# DualDriverProp.net
KiCad netlist of a schematic drawn in Altium Designer
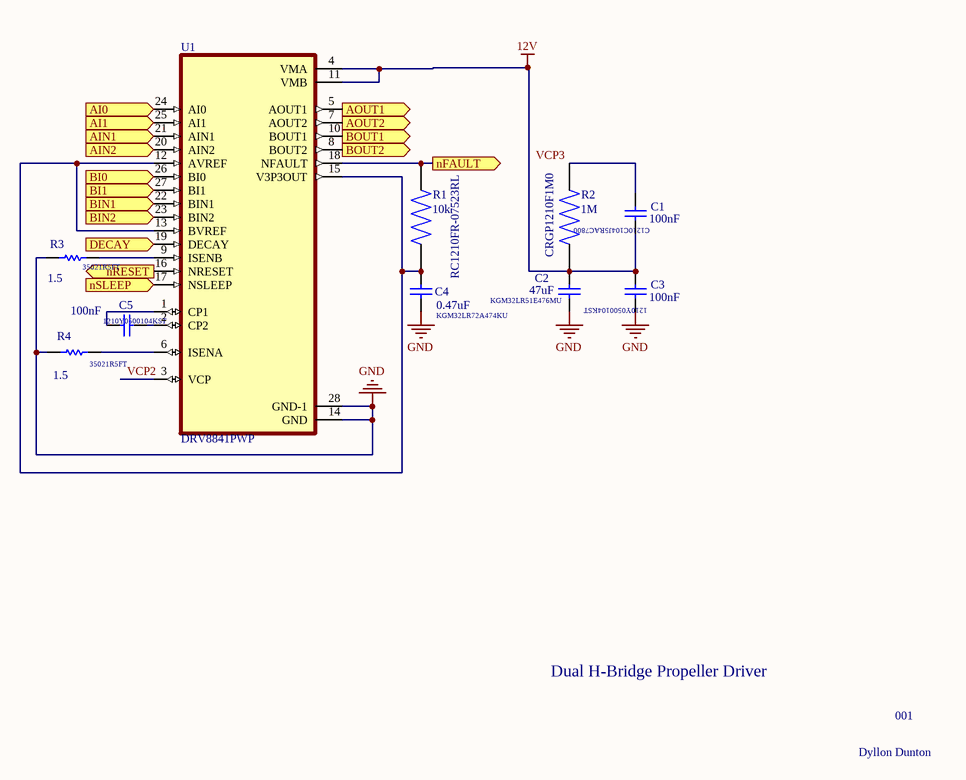
[diagram p0: DualDriverProp.SchDoc]

(export (version "E")
  (design (tool "Eeschema 10.0.6"))
  (components
    (comp (ref "C1")
      (value "100nF")
      (footprint "C1210")
      (description "Capacitor")
      (fields (field (name "Comment") "Cap") (field (name "PUBLISHER") "Altium Limited"))
      (libsource (lib "Miscellaneous Devices") (part "Cap"))
    )
    (comp (ref "C2")
      (value "47uF")
      (footprint "C1210")
      (description "Capacitor")
      (fields (field (name "Comment") "Cap") (field (name "PUBLISHER") "Altium Limited"))
      (libsource (lib "Miscellaneous Devices") (part "Cap"))
    )
    (comp (ref "C3")
      (value "100nF")
      (footprint "C1210")
      (description "Capacitor")
      (fields (field (name "Comment") "Cap") (field (name "PUBLISHER") "Altium Limited"))
      (libsource (lib "Miscellaneous Devices") (part "Cap"))
    )
    (comp (ref "C4")
      (value "0.47uF")
      (footprint "C1210")
      (description "Capacitor")
      (fields (field (name "Comment") "Cap") (field (name "PUBLISHER") "Altium Limited"))
      (libsource (lib "Miscellaneous Devices") (part "Cap"))
    )
    (comp (ref "C5")
      (value "100nF")
      (footprint "C1210")
      (description "Capacitor")
      (fields (field (name "Comment") "Cap") (field (name "PUBLISHER") "Altium Limited"))
      (libsource (lib "Miscellaneous Devices") (part "Cap"))
    )
    (comp (ref "R1")
      (value "RC1210FR-07523RL")
      (footprint "RESC3126X65N")
      (description "523 Ohms Â±1% 0.5W, 1/2W Chip Resistor 1210 _3225 Metric_ Moisture Resistant Thick Film")
      (fields (field (name "MF") "Yageo") (field (name "ALTIUM_VALUE") "10k"))
      (libsource (lib "RC1210FR-07523RL") (part "RC1210FR-07523RL"))
    )
    (comp (ref "R2")
      (value "CRGP1210F1M0")
      (footprint "RESC3126X65N")
      (description "523 Ohms Â±1% 0.5W, 1/2W Chip Resistor 1210 _3225 Metric_ Moisture Resistant Thick Film")
      (fields
        (field (name "MF") "Yageo")
        (field (name "ALTIUM_VALUE") "1M")
        (field (name "MP") "RC1210FR-07523RL")
      )
      (libsource (lib "RC1210FR-07523RL") (part "RC1210FR-07523RL"))
    )
    (comp (ref "R3")
      (value "1.5")
      (footprint "RESC5025X70N")
      (description "Resistor")
      (fields (field (name "Comment") "Res1") (field (name "PUBLISHER") "Altium Limited"))
      (libsource (lib "Miscellaneous Devices") (part "Res1"))
    )
    (comp (ref "R4")
      (value "1.5")
      (footprint "RESC5025X70N")
      (description "Resistor")
      (fields (field (name "Comment") "Res1") (field (name "PUBLISHER") "Altium Limited"))
      (libsource (lib "Miscellaneous Devices") (part "Res1"))
    )
    (comp (ref "U1")
      (value "DRV8841PWP")
      (footprint "IC_TPS61196PWPRQ1")
      (fields (field (name "MF") "Texas Instruments"))
      (libsource (lib "DRV8841PWP") (part "DRV8841PWP"))
    )
  )
  (nets
    (net (code "1") (name "/AI0") (class "Default")
      (node (ref "U1") (pin "24") (pinfunction "AI0_24") (pintype "input"))
    )
    (net (code "2") (name "/AI1") (class "Default")
      (node (ref "U1") (pin "25") (pinfunction "AI1_25") (pintype "input"))
    )
    (net (code "3") (name "/AIN1") (class "Default")
      (node (ref "U1") (pin "21") (pinfunction "AIN1_21") (pintype "input"))
    )
    (net (code "4") (name "/AIN2") (class "Default")
      (node (ref "U1") (pin "20") (pinfunction "AIN2_20") (pintype "input"))
    )
    (net (code "5") (name "/AOUT1") (class "Default")
      (node (ref "U1") (pin "5") (pinfunction "AOUT1_5") (pintype "output"))
    )
    (net (code "6") (name "/AOUT2") (class "Default")
      (node (ref "U1") (pin "7") (pinfunction "AOUT2_7") (pintype "output"))
    )
    (net (code "7") (name "/BI0") (class "Default")
      (node (ref "U1") (pin "26") (pinfunction "BI0_26") (pintype "input"))
    )
    (net (code "8") (name "/BI1") (class "Default")
      (node (ref "U1") (pin "27") (pinfunction "BI1_27") (pintype "input"))
    )
    (net (code "9") (name "/BIN1") (class "Default")
      (node (ref "U1") (pin "22") (pinfunction "BIN1_22") (pintype "input"))
    )
    (net (code "10") (name "/BIN2") (class "Default")
      (node (ref "U1") (pin "23") (pinfunction "BIN2_23") (pintype "input"))
    )
    (net (code "11") (name "/BOUT1") (class "Default")
      (node (ref "U1") (pin "10") (pinfunction "BOUT1_10") (pintype "output"))
    )
    (net (code "12") (name "/BOUT2") (class "Default")
      (node (ref "U1") (pin "8") (pinfunction "BOUT2_8") (pintype "output"))
    )
    (net (code "13") (name "/DECAY") (class "Default")
      (node (ref "U1") (pin "19") (pinfunction "DECAY_19") (pintype "input"))
    )
    (net (code "14") (name "/VCP2") (class "Default")
      (node (ref "U1") (pin "3") (pinfunction "VCP_3") (pintype "bidirectional"))
    )
    (net (code "16") (name "/nFAULT") (class "Default")
      (node (ref "R1") (pin "2") (pinfunction "2_2") (pintype "passive"))
      (node (ref "U1") (pin "18") (pinfunction "NFAULT_18") (pintype "output"))
    )
    (net (code "17") (name "/nRESET") (class "Default")
      (node (ref "U1") (pin "16") (pinfunction "NRESET_16") (pintype "input"))
    )
    (net (code "18") (name "/nSLEEP") (class "Default")
      (node (ref "U1") (pin "17") (pinfunction "NSLEEP_17") (pintype "input"))
    )
    (net (code "19") (name "12V") (class "Default")
      (node (ref "C1") (pin "2") (pinfunction "2_2") (pintype "passive"))
      (node (ref "C2") (pin "2") (pinfunction "2_2") (pintype "passive"))
      (node (ref "C3") (pin "1") (pinfunction "1_1") (pintype "passive"))
      (node (ref "R2") (pin "1") (pinfunction "1_1") (pintype "passive"))
      (node (ref "U1") (pin "11") (pinfunction "VMB_11") (pintype "power_in"))
      (node (ref "U1") (pin "4") (pinfunction "VMA_4") (pintype "power_in"))
    )
    (net (code "20") (name "GND") (class "Default")
      (node (ref "C2") (pin "1") (pinfunction "1_1") (pintype "passive"))
      (node (ref "C3") (pin "2") (pinfunction "2_2") (pintype "passive"))
      (node (ref "C4") (pin "1") (pinfunction "1_1") (pintype "passive"))
      (node (ref "R3") (pin "1") (pinfunction "1_1") (pintype "passive"))
      (node (ref "R4") (pin "1") (pinfunction "1_1") (pintype "passive"))
      (node (ref "U1") (pin "14") (pinfunction "GND_14") (pintype "power_in"))
      (node (ref "U1") (pin "28") (pinfunction "GND-1_28") (pintype "power_in"))
    )
    (net (code "21") (name "Net-(C1-Pad1)") (class "Default")
      (node (ref "C1") (pin "1") (pinfunction "1_1") (pintype "passive"))
      (node (ref "R2") (pin "2") (pinfunction "2_2") (pintype "passive"))
    )
    (net (code "22") (name "Net-(U1-AVREF)") (class "Default")
      (node (ref "C4") (pin "2") (pinfunction "2_2") (pintype "passive"))
      (node (ref "R1") (pin "1") (pinfunction "1_1") (pintype "passive"))
      (node (ref "U1") (pin "12") (pinfunction "AVREF_12") (pintype "input"))
      (node (ref "U1") (pin "13") (pinfunction "BVREF_13") (pintype "input"))
      (node (ref "U1") (pin "15") (pinfunction "V3P3OUT_15") (pintype "output"))
    )
    (net (code "23") (name "Net-(U1-CP1)") (class "Default")
      (node (ref "C5") (pin "2") (pinfunction "2_2") (pintype "passive"))
      (node (ref "U1") (pin "1") (pinfunction "CP1_1") (pintype "bidirectional"))
    )
    (net (code "24") (name "Net-(U1-CP2)") (class "Default")
      (node (ref "C5") (pin "1") (pinfunction "1_1") (pintype "passive"))
      (node (ref "U1") (pin "2") (pinfunction "CP2_2") (pintype "bidirectional"))
    )
    (net (code "25") (name "Net-(U1-ISENA)") (class "Default")
      (node (ref "R4") (pin "2") (pinfunction "2_2") (pintype "passive"))
      (node (ref "U1") (pin "6") (pinfunction "ISENA_6") (pintype "bidirectional"))
    )
    (net (code "26") (name "Net-(U1-ISENB)") (class "Default")
      (node (ref "R3") (pin "2") (pinfunction "2_2") (pintype "passive"))
      (node (ref "U1") (pin "9") (pinfunction "ISENB_9") (pintype "input"))
    )
  )
)
